# od1.net
KiCad netlist of a schematic drawn in EAGLE
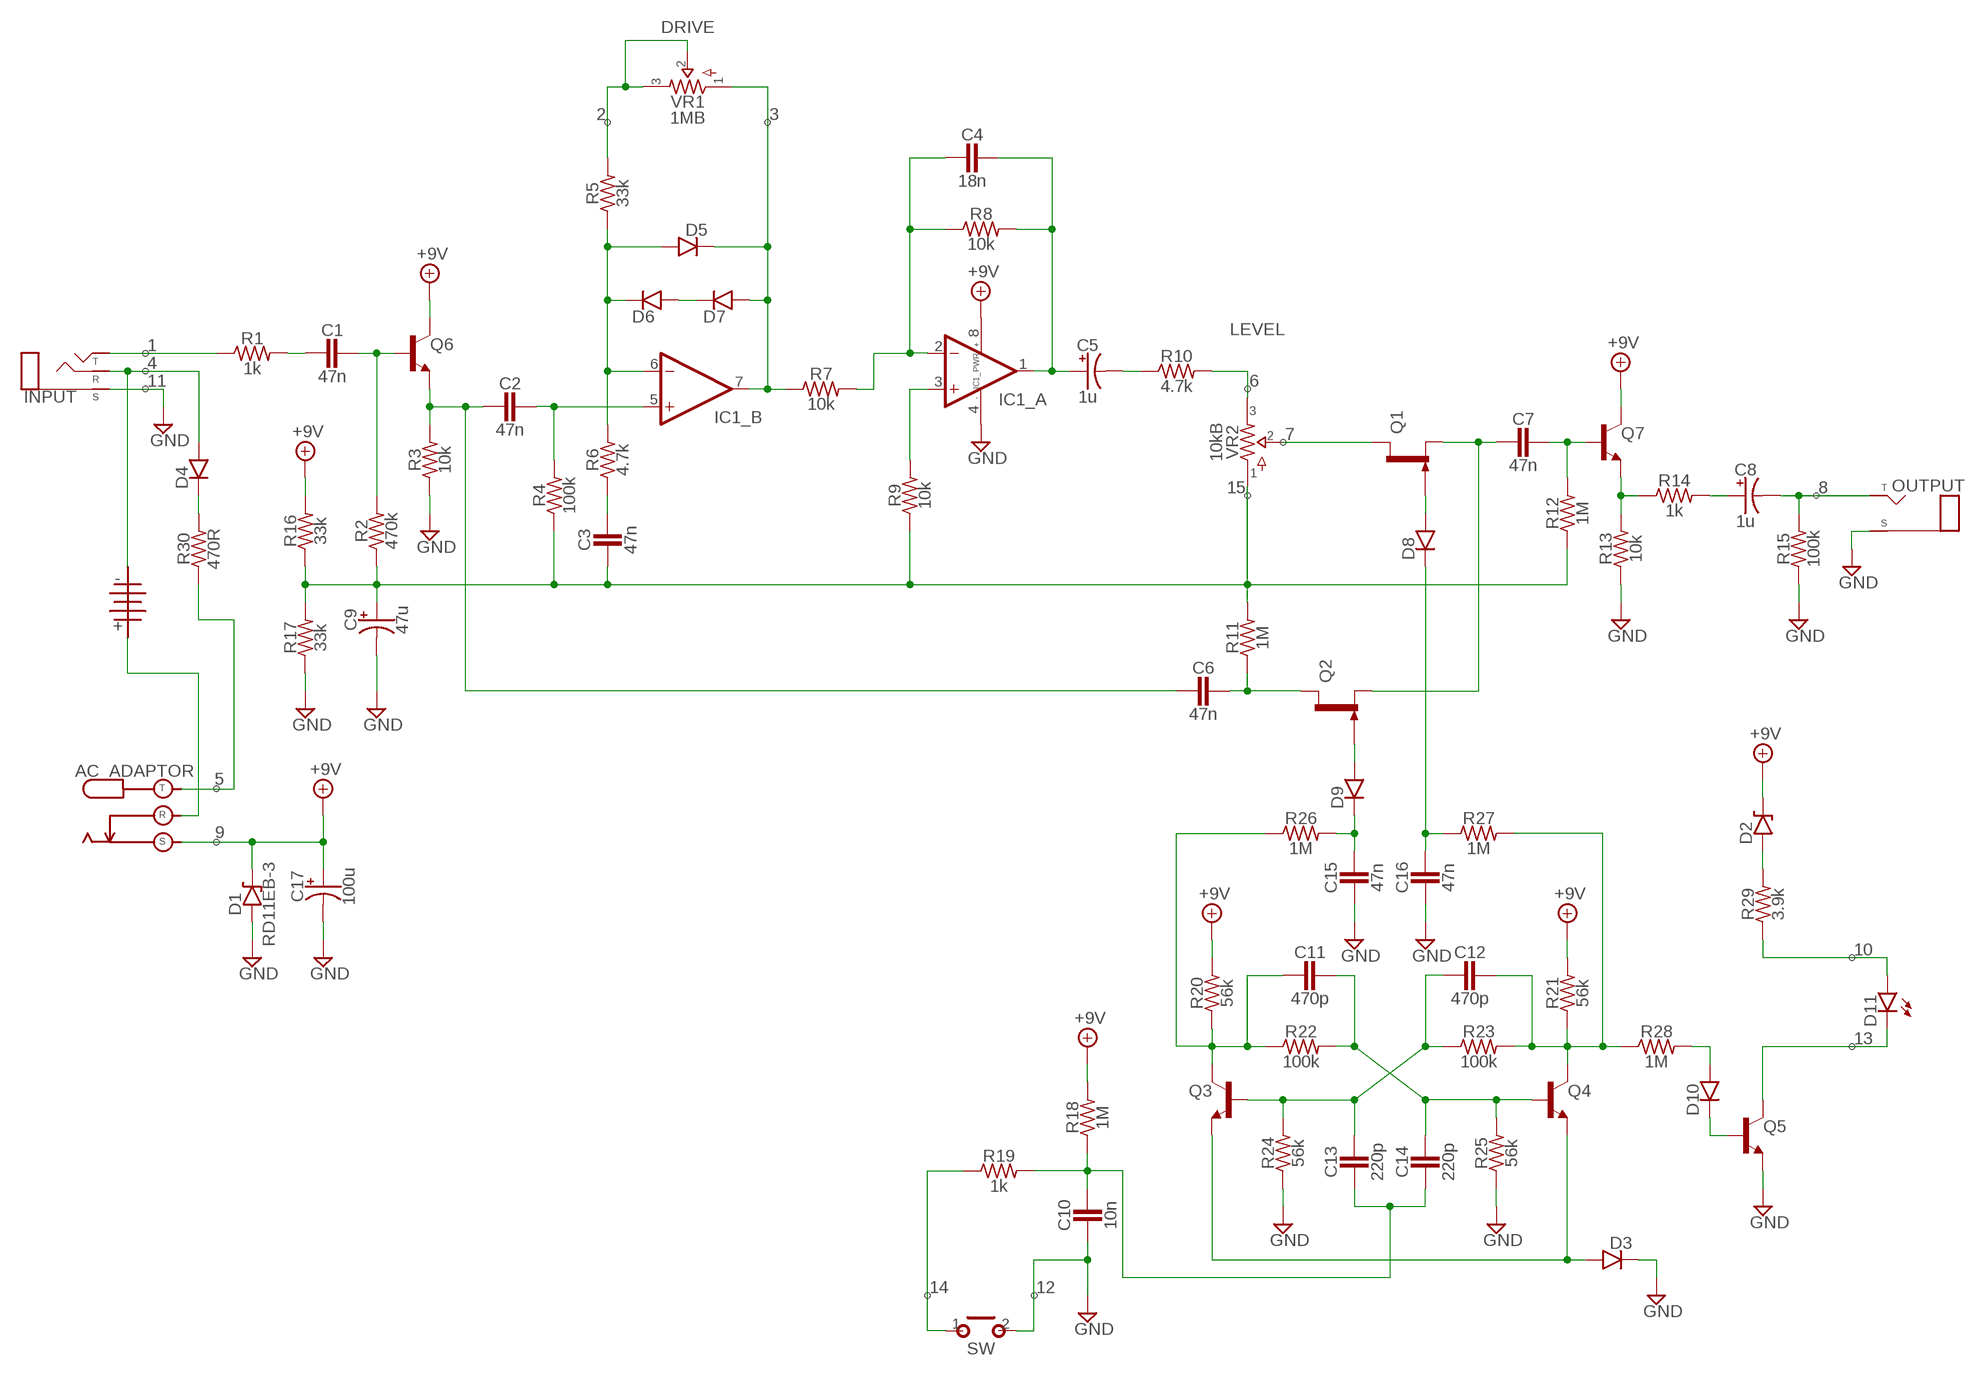
[diagram p0: schematic, sheet 1]

(export (version "E")
  (design (tool "Eeschema 10.0.6"))
  (components
    (comp (ref "1101")
      (value "BATTERY")
      (footprint "eagle-import:TWO_PADS")
      (libsource (lib "eagle-import") (part "BATTERY"))
    )
    (comp (ref "AC_ADAPTOR")
      (value "DC_KOBICONN")
      (footprint "eagle-import:DC_KOBICONN")
      (libsource (lib "eagle-import") (part "DC_KOBICONN"))
    )
    (comp (ref "C1")
      (value "47n")
      (footprint "eagle-import:BOX_SMALL")
      (libsource (lib "eagle-import") (part "CER/FILMBOX.1"))
    )
    (comp (ref "C2")
      (value "47n")
      (footprint "eagle-import:BOX_SMALL")
      (libsource (lib "eagle-import") (part "CER/FILMBOX.1"))
    )
    (comp (ref "C3")
      (value "47n")
      (footprint "eagle-import:BOX_SMALL")
      (libsource (lib "eagle-import") (part "CER/FILMBOX.1"))
    )
    (comp (ref "C4")
      (value "18n")
      (footprint "eagle-import:BOX_SMALL")
      (libsource (lib "eagle-import") (part "CER/FILMBOX.1"))
    )
    (comp (ref "C5")
      (value "1u")
      (footprint "eagle-import:040_020")
      (libsource (lib "eagle-import") (part "0400"))
    )
    (comp (ref "C6")
      (value "47n")
      (footprint "eagle-import:BOX_SMALL")
      (libsource (lib "eagle-import") (part "CER/FILMBOX.1"))
    )
    (comp (ref "C7")
      (value "47n")
      (footprint "eagle-import:BOX_SMALL")
      (libsource (lib "eagle-import") (part "CER/FILMBOX.1"))
    )
    (comp (ref "C8")
      (value "1u")
      (footprint "eagle-import:040_020")
      (libsource (lib "eagle-import") (part "0400"))
    )
    (comp (ref "C9")
      (value "47u")
      (footprint "eagle-import:040_020")
      (libsource (lib "eagle-import") (part "0400"))
    )
    (comp (ref "C10")
      (value "10n")
      (footprint "eagle-import:BOX_SMALL")
      (libsource (lib "eagle-import") (part "CER/FILMBOX.1"))
    )
    (comp (ref "C11")
      (value "470p")
      (footprint "eagle-import:BOX_SMALL")
      (libsource (lib "eagle-import") (part "CER/FILMBOX.1"))
    )
    (comp (ref "C12")
      (value "470p")
      (footprint "eagle-import:BOX_SMALL")
      (libsource (lib "eagle-import") (part "CER/FILMBOX.1"))
    )
    (comp (ref "C13")
      (value "220p")
      (footprint "eagle-import:BOX_SMALL")
      (libsource (lib "eagle-import") (part "CER/FILMBOX.1"))
    )
    (comp (ref "C14")
      (value "220p")
      (footprint "eagle-import:BOX_SMALL")
      (libsource (lib "eagle-import") (part "CER/FILMBOX.1"))
    )
    (comp (ref "C15")
      (value "47n")
      (footprint "eagle-import:BOX_SMALL")
      (libsource (lib "eagle-import") (part "CER/FILMBOX.1"))
    )
    (comp (ref "C16")
      (value "47n")
      (footprint "eagle-import:BOX_SMALL")
      (libsource (lib "eagle-import") (part "CER/FILMBOX.1"))
    )
    (comp (ref "C17")
      (value "100u")
      (footprint "eagle-import:040_020")
      (libsource (lib "eagle-import") (part "0400"))
    )
    (comp (ref "D1")
      (value "RD11EB-3")
      (footprint "eagle-import:DO41-2")
      (libsource (lib "eagle-import") (part "ZENER.2"))
    )
    (comp (ref "D2")
      (value "ZENER.2")
      (footprint "eagle-import:DO41-2")
      (libsource (lib "eagle-import") (part "ZENER.2"))
    )
    (comp (ref "D3")
      (value "DO35.2")
      (footprint "eagle-import:DO35-2")
      (libsource (lib "eagle-import") (part "DO35.2"))
    )
    (comp (ref "D4")
      (value "DO35.2")
      (footprint "eagle-import:DO35-2")
      (libsource (lib "eagle-import") (part "DO35.2"))
    )
    (comp (ref "D5")
      (value "DO35.2")
      (footprint "eagle-import:DO35-2")
      (libsource (lib "eagle-import") (part "DO35.2"))
    )
    (comp (ref "D6")
      (value "DO35.2")
      (footprint "eagle-import:DO35-2")
      (libsource (lib "eagle-import") (part "DO35.2"))
    )
    (comp (ref "D7")
      (value "DO35.2")
      (footprint "eagle-import:DO35-2")
      (libsource (lib "eagle-import") (part "DO35.2"))
    )
    (comp (ref "D8")
      (value "DO35.2")
      (footprint "eagle-import:DO35-2")
      (libsource (lib "eagle-import") (part "DO35.2"))
    )
    (comp (ref "D9")
      (value "DO35.2")
      (footprint "eagle-import:DO35-2")
      (libsource (lib "eagle-import") (part "DO35.2"))
    )
    (comp (ref "D10")
      (value "DO35.2")
      (footprint "eagle-import:DO35-2")
      (libsource (lib "eagle-import") (part "DO35.2"))
    )
    (comp (ref "D11")
      (value "SLP1358")
      (footprint "eagle-import:3MM_D")
      (libsource (lib "eagle-import") (part "LED"))
    )
    (comp (ref "IC1")
      (value "DUALTH")
      (footprint "eagle-import:DIL0")
      (libsource (lib "eagle-import") (part "DUALTH"))
    )
    (comp (ref "INPUT")
      (value "STEREO3PADS")
      (footprint "eagle-import:THREEPADS")
      (libsource (lib "eagle-import") (part "STEREO3PADS"))
    )
    (comp (ref "OUTPUT")
      (value "MONO")
      (footprint "eagle-import:TWO_PADS")
      (libsource (lib "eagle-import") (part "MONO"))
    )
    (comp (ref "Q1")
      (value "2N5457")
      (footprint "eagle-import:TO92-")
      (libsource (lib "eagle-import") (part "2N5457"))
    )
    (comp (ref "Q2")
      (value "2N5457")
      (footprint "eagle-import:TO92-")
      (libsource (lib "eagle-import") (part "2N5457"))
    )
    (comp (ref "Q3")
      (value "2SC828A")
      (footprint "eagle-import:TO92-")
      (libsource (lib "eagle-import") (part "2SC828A"))
    )
    (comp (ref "Q4")
      (value "2SC828A")
      (footprint "eagle-import:TO92-")
      (libsource (lib "eagle-import") (part "2SC828A"))
    )
    (comp (ref "Q5")
      (value "2SC828A")
      (footprint "eagle-import:TO92-")
      (libsource (lib "eagle-import") (part "2SC828A"))
    )
    (comp (ref "Q6")
      (value "2SC828A")
      (footprint "eagle-import:TO92-")
      (libsource (lib "eagle-import") (part "2SC828A"))
    )
    (comp (ref "Q7")
      (value "2SC828A")
      (footprint "eagle-import:TO92-")
      (libsource (lib "eagle-import") (part "2SC828A"))
    )
    (comp (ref "R1")
      (value "1k")
      (footprint "eagle-import:R0207_3")
      (libsource (lib "eagle-import") (part "R_.3B"))
    )
    (comp (ref "R2")
      (value "470k")
      (footprint "eagle-import:R0207_3")
      (libsource (lib "eagle-import") (part "R_.3B"))
    )
    (comp (ref "R3")
      (value "10k")
      (footprint "eagle-import:R0207_3")
      (libsource (lib "eagle-import") (part "R_.3B"))
    )
    (comp (ref "R4")
      (value "100k")
      (footprint "eagle-import:R0207_3")
      (libsource (lib "eagle-import") (part "R_.3B"))
    )
    (comp (ref "R5")
      (value "33k")
      (footprint "eagle-import:R0207_3")
      (libsource (lib "eagle-import") (part "R_.3B"))
    )
    (comp (ref "R6")
      (value "4.7k")
      (footprint "eagle-import:R0207_3")
      (libsource (lib "eagle-import") (part "R_.3B"))
    )
    (comp (ref "R7")
      (value "10k")
      (footprint "eagle-import:R0207_3")
      (libsource (lib "eagle-import") (part "R_.3B"))
    )
    (comp (ref "R8")
      (value "10k")
      (footprint "eagle-import:R0207_3")
      (libsource (lib "eagle-import") (part "R_.3B"))
    )
    (comp (ref "R9")
      (value "10k")
      (footprint "eagle-import:R0207_3")
      (libsource (lib "eagle-import") (part "R_.3B"))
    )
    (comp (ref "R10")
      (value "4.7k")
      (footprint "eagle-import:R0207_3")
      (libsource (lib "eagle-import") (part "R_.3B"))
    )
    (comp (ref "R11")
      (value "1M")
      (footprint "eagle-import:R0207_3")
      (libsource (lib "eagle-import") (part "R_.3B"))
    )
    (comp (ref "R12")
      (value "1M")
      (footprint "eagle-import:R0207_3")
      (libsource (lib "eagle-import") (part "R_.3B"))
    )
    (comp (ref "R13")
      (value "10k")
      (footprint "eagle-import:R0207_3")
      (libsource (lib "eagle-import") (part "R_.3B"))
    )
    (comp (ref "R14")
      (value "1k")
      (footprint "eagle-import:R0207_3")
      (libsource (lib "eagle-import") (part "R_.3B"))
    )
    (comp (ref "R15")
      (value "100k")
      (footprint "eagle-import:R0207_3")
      (libsource (lib "eagle-import") (part "R_.3B"))
    )
    (comp (ref "R16")
      (value "33k")
      (footprint "eagle-import:R0207_3")
      (libsource (lib "eagle-import") (part "R_.3B"))
    )
    (comp (ref "R17")
      (value "33k")
      (footprint "eagle-import:R0207_3")
      (libsource (lib "eagle-import") (part "R_.3B"))
    )
    (comp (ref "R18")
      (value "1M")
      (footprint "eagle-import:R0207_3")
      (libsource (lib "eagle-import") (part "R_.3B"))
    )
    (comp (ref "R19")
      (value "1k")
      (footprint "eagle-import:R0207_3")
      (libsource (lib "eagle-import") (part "R_.3B"))
    )
    (comp (ref "R20")
      (value "56k")
      (footprint "eagle-import:R0207_3")
      (libsource (lib "eagle-import") (part "R_.3B"))
    )
    (comp (ref "R21")
      (value "56k")
      (footprint "eagle-import:R0207_3")
      (libsource (lib "eagle-import") (part "R_.3B"))
    )
    (comp (ref "R22")
      (value "100k")
      (footprint "eagle-import:R0207_3")
      (libsource (lib "eagle-import") (part "R_.3B"))
    )
    (comp (ref "R23")
      (value "100k")
      (footprint "eagle-import:R0207_3")
      (libsource (lib "eagle-import") (part "R_.3B"))
    )
    (comp (ref "R24")
      (value "56k")
      (footprint "eagle-import:R0207_3")
      (libsource (lib "eagle-import") (part "R_.3B"))
    )
    (comp (ref "R25")
      (value "56k")
      (footprint "eagle-import:R0207_3")
      (libsource (lib "eagle-import") (part "R_.3B"))
    )
    (comp (ref "R26")
      (value "1M")
      (footprint "eagle-import:R0207_3")
      (libsource (lib "eagle-import") (part "R_.3B"))
    )
    (comp (ref "R27")
      (value "1M")
      (footprint "eagle-import:R0207_3")
      (libsource (lib "eagle-import") (part "R_.3B"))
    )
    (comp (ref "R28")
      (value "1M")
      (footprint "eagle-import:R0207_3")
      (libsource (lib "eagle-import") (part "R_.3B"))
    )
    (comp (ref "R29")
      (value "3.9k")
      (footprint "eagle-import:R0207_3")
      (libsource (lib "eagle-import") (part "R_.3B"))
    )
    (comp (ref "R30")
      (value "470R")
      (footprint "eagle-import:R0207_3")
      (libsource (lib "eagle-import") (part "R_.3B"))
    )
    (comp (ref "SW")
      (value "MOMENTARY")
      (footprint "eagle-import:SPST")
      (libsource (lib "eagle-import") (part "MOMENTARY"))
    )
    (comp (ref "VR1")
      (value "1MB")
      (footprint "eagle-import:16MM")
      (libsource (lib "eagle-import") (part "POTS16MM"))
    )
    (comp (ref "VR2")
      (value "10kB")
      (footprint "eagle-import:16MM")
      (libsource (lib "eagle-import") (part "POTS16MM"))
    )
  )
  (nets
    (net (code "1") (name "+9V") (class "Default")
      (node (ref "AC_ADAPTOR") (pin "S") (pinfunction "S_S") (pintype "bidirectional"))
      (node (ref "C17") (pin "+") (pinfunction "+_+") (pintype "passive"))
      (node (ref "D1") (pin "C") (pinfunction "C_C") (pintype "passive"))
      (node (ref "D2") (pin "C") (pinfunction "C_C") (pintype "passive"))
      (node (ref "IC1") (pin "8") (pinfunction "V+_8") (pintype "power_in"))
      (node (ref "Q6") (pin "2") (pinfunction "C_2") (pintype "passive"))
      (node (ref "Q7") (pin "2") (pinfunction "C_2") (pintype "passive"))
      (node (ref "R16") (pin "2") (pinfunction "2_2") (pintype "passive"))
      (node (ref "R18") (pin "2") (pinfunction "2_2") (pintype "passive"))
      (node (ref "R20") (pin "2") (pinfunction "2_2") (pintype "passive"))
      (node (ref "R21") (pin "2") (pinfunction "2_2") (pintype "passive"))
    )
    (net (code "2") (name "GND") (class "Default")
      (node (ref "C10") (pin "2") (pinfunction "2_2") (pintype "passive"))
      (node (ref "C15") (pin "2") (pinfunction "2_2") (pintype "passive"))
      (node (ref "C16") (pin "2") (pinfunction "2_2") (pintype "passive"))
      (node (ref "C17") (pin "-") (pinfunction "-_-") (pintype "passive"))
      (node (ref "C9") (pin "-") (pinfunction "-_-") (pintype "passive"))
      (node (ref "D1") (pin "A") (pinfunction "A_A") (pintype "passive"))
      (node (ref "D3") (pin "C") (pinfunction "C_C") (pintype "passive"))
      (node (ref "IC1") (pin "4") (pinfunction "V-_4") (pintype "power_in"))
      (node (ref "INPUT") (pin "SLEEVE") (pinfunction "S_SLEEVE") (pintype "passive"))
      (node (ref "OUTPUT") (pin "S") (pinfunction "SLEEVE_S") (pintype "passive"))
      (node (ref "Q5") (pin "3") (pinfunction "E_3") (pintype "passive"))
      (node (ref "R13") (pin "1") (pinfunction "1_1") (pintype "passive"))
      (node (ref "R15") (pin "1") (pinfunction "1_1") (pintype "passive"))
      (node (ref "R17") (pin "1") (pinfunction "1_1") (pintype "passive"))
      (node (ref "R24") (pin "1") (pinfunction "1_1") (pintype "passive"))
      (node (ref "R25") (pin "1") (pinfunction "1_1") (pintype "passive"))
      (node (ref "R3") (pin "1") (pinfunction "1_1") (pintype "passive"))
      (node (ref "SW") (pin "2") (pinfunction "S_2") (pintype "passive"))
    )
    (net (code "3") (name "Net-(1101-P$1)") (class "Default")
      (node (ref "1101") (pin "T") (pinfunction "P$1_T") (pintype "bidirectional"))
      (node (ref "AC_ADAPTOR") (pin "R") (pinfunction "R_R") (pintype "bidirectional"))
    )
    (net (code "4") (name "Net-(1101-P$2)") (class "Default")
      (node (ref "1101") (pin "S") (pinfunction "P$2_S") (pintype "bidirectional"))
      (node (ref "D4") (pin "A") (pinfunction "A_A") (pintype "passive"))
      (node (ref "INPUT") (pin "RING") (pinfunction "R_RING") (pintype "passive"))
    )
    (net (code "5") (name "Net-(AC_ADAPTOR-PadT)") (class "Default")
      (node (ref "AC_ADAPTOR") (pin "T") (pinfunction "T_T") (pintype "bidirectional"))
      (node (ref "R30") (pin "1") (pinfunction "1_1") (pintype "passive"))
    )
    (net (code "6") (name "Net-(C1-Pad2)") (class "Default")
      (node (ref "C1") (pin "2") (pinfunction "2_2") (pintype "passive"))
      (node (ref "R1") (pin "2") (pinfunction "2_2") (pintype "passive"))
    )
    (net (code "7") (name "Net-(C3-Pad1)") (class "Default")
      (node (ref "C3") (pin "1") (pinfunction "1_1") (pintype "passive"))
      (node (ref "R6") (pin "1") (pinfunction "1_1") (pintype "passive"))
    )
    (net (code "8") (name "Net-(C3-Pad2)") (class "Default")
      (node (ref "C3") (pin "2") (pinfunction "2_2") (pintype "passive"))
      (node (ref "C9") (pin "+") (pinfunction "+_+") (pintype "passive"))
      (node (ref "R11") (pin "2") (pinfunction "2_2") (pintype "passive"))
      (node (ref "R12") (pin "1") (pinfunction "1_1") (pintype "passive"))
      (node (ref "R16") (pin "1") (pinfunction "1_1") (pintype "passive"))
      (node (ref "R17") (pin "2") (pinfunction "2_2") (pintype "passive"))
      (node (ref "R2") (pin "1") (pinfunction "1_1") (pintype "passive"))
      (node (ref "R4") (pin "1") (pinfunction "1_1") (pintype "passive"))
      (node (ref "R9") (pin "1") (pinfunction "1_1") (pintype "passive"))
      (node (ref "VR2") (pin "1") (pinfunction "1_1") (pintype "passive"))
    )
    (net (code "9") (name "Net-(C5-Pad-)") (class "Default")
      (node (ref "C5") (pin "-") (pinfunction "-_-") (pintype "passive"))
      (node (ref "R10") (pin "1") (pinfunction "1_1") (pintype "passive"))
    )
    (net (code "10") (name "Net-(C8-Pad+)") (class "Default")
      (node (ref "C8") (pin "+") (pinfunction "+_+") (pintype "passive"))
      (node (ref "R14") (pin "2") (pinfunction "2_2") (pintype "passive"))
    )
    (net (code "11") (name "Net-(C10-Pad1)") (class "Default")
      (node (ref "C10") (pin "1") (pinfunction "1_1") (pintype "passive"))
      (node (ref "C13") (pin "2") (pinfunction "2_2") (pintype "passive"))
      (node (ref "C14") (pin "2") (pinfunction "2_2") (pintype "passive"))
      (node (ref "R18") (pin "1") (pinfunction "1_1") (pintype "passive"))
      (node (ref "R19") (pin "2") (pinfunction "2_2") (pintype "passive"))
    )
    (net (code "12") (name "Net-(C15-Pad1)") (class "Default")
      (node (ref "C15") (pin "1") (pinfunction "1_1") (pintype "passive"))
      (node (ref "D9") (pin "C") (pinfunction "C_C") (pintype "passive"))
      (node (ref "R26") (pin "2") (pinfunction "2_2") (pintype "passive"))
    )
    (net (code "13") (name "Net-(C16-Pad1)") (class "Default")
      (node (ref "C16") (pin "1") (pinfunction "1_1") (pintype "passive"))
      (node (ref "D8") (pin "C") (pinfunction "C_C") (pintype "passive"))
      (node (ref "R27") (pin "1") (pinfunction "1_1") (pintype "passive"))
    )
    (net (code "14") (name "Net-(D2-PadA)") (class "Default")
      (node (ref "D2") (pin "A") (pinfunction "A_A") (pintype "passive"))
      (node (ref "R29") (pin "2") (pinfunction "2_2") (pintype "passive"))
    )
    (net (code "15") (name "Net-(D4-PadC)") (class "Default")
      (node (ref "D4") (pin "C") (pinfunction "C_C") (pintype "passive"))
      (node (ref "R30") (pin "2") (pinfunction "2_2") (pintype "passive"))
    )
    (net (code "16") (name "Net-(D6-PadA)") (class "Default")
      (node (ref "D6") (pin "A") (pinfunction "A_A") (pintype "passive"))
      (node (ref "D7") (pin "C") (pinfunction "C_C") (pintype "passive"))
    )
    (net (code "17") (name "Net-(D10-PadA)") (class "Default")
      (node (ref "D10") (pin "A") (pinfunction "A_A") (pintype "passive"))
      (node (ref "R28") (pin "2") (pinfunction "2_2") (pintype "passive"))
    )
    (net (code "18") (name "Net-(D11-A)") (class "Default")
      (node (ref "D11") (pin "ANODE") (pinfunction "A_ANODE") (pintype "passive"))
      (node (ref "R29") (pin "1") (pinfunction "1_1") (pintype "passive"))
    )
    (net (code "19") (name "Net-(D11-C)") (class "Default")
      (node (ref "D11") (pin "P$1") (pinfunction "C_P$1") (pintype "passive"))
      (node (ref "Q5") (pin "2") (pinfunction "C_2") (pintype "passive"))
    )
    (net (code "20") (name "Net-(IC1A-+IN)") (class "Default")
      (node (ref "IC1") (pin "3") (pinfunction "+IN_3") (pintype "input"))
      (node (ref "R9") (pin "2") (pinfunction "2_2") (pintype "passive"))
    )
    (net (code "21") (name "Net-(IC1A--IN)") (class "Default")
      (node (ref "C4") (pin "2") (pinfunction "2_2") (pintype "passive"))
      (node (ref "IC1") (pin "2") (pinfunction "-IN_2") (pintype "input"))
      (node (ref "R7") (pin "2") (pinfunction "2_2") (pintype "passive"))
      (node (ref "R8") (pin "1") (pinfunction "1_1") (pintype "passive"))
    )
    (net (code "22") (name "Net-(IC1A-OUT)") (class "Default")
      (node (ref "C4") (pin "1") (pinfunction "1_1") (pintype "passive"))
      (node (ref "C5") (pin "+") (pinfunction "+_+") (pintype "passive"))
      (node (ref "IC1") (pin "1") (pinfunction "OUT_1") (pintype "output"))
      (node (ref "R8") (pin "2") (pinfunction "2_2") (pintype "passive"))
    )
    (net (code "23") (name "Net-(IC1B-+IN)") (class "Default")
      (node (ref "C2") (pin "1") (pinfunction "1_1") (pintype "passive"))
      (node (ref "IC1") (pin "5") (pinfunction "+IN_5") (pintype "input"))
      (node (ref "R4") (pin "2") (pinfunction "2_2") (pintype "passive"))
    )
    (net (code "24") (name "Net-(IC1B--IN)") (class "Default")
      (node (ref "D5") (pin "A") (pinfunction "A_A") (pintype "passive"))
      (node (ref "D6") (pin "C") (pinfunction "C_C") (pintype "passive"))
      (node (ref "IC1") (pin "6") (pinfunction "-IN_6") (pintype "input"))
      (node (ref "R5") (pin "1") (pinfunction "1_1") (pintype "passive"))
      (node (ref "R6") (pin "2") (pinfunction "2_2") (pintype "passive"))
    )
    (net (code "25") (name "Net-(IC1B-OUT)") (class "Default")
      (node (ref "D5") (pin "C") (pinfunction "C_C") (pintype "passive"))
      (node (ref "D7") (pin "A") (pinfunction "A_A") (pintype "passive"))
      (node (ref "IC1") (pin "7") (pinfunction "OUT_7") (pintype "output"))
      (node (ref "R7") (pin "1") (pinfunction "1_1") (pintype "passive"))
      (node (ref "VR1") (pin "1") (pinfunction "1_1") (pintype "passive"))
    )
    (net (code "26") (name "Net-(INPUT-T)") (class "Default")
      (node (ref "INPUT") (pin "TIP") (pinfunction "T_TIP") (pintype "passive"))
      (node (ref "R1") (pin "1") (pinfunction "1_1") (pintype "passive"))
    )
    (net (code "27") (name "Net-(OUTPUT-TIP)") (class "Default")
      (node (ref "C8") (pin "-") (pinfunction "-_-") (pintype "passive"))
      (node (ref "OUTPUT") (pin "T") (pinfunction "TIP_T") (pintype "passive"))
      (node (ref "R15") (pin "2") (pinfunction "2_2") (pintype "passive"))
    )
    (net (code "28") (name "Net-(Q1-D)") (class "Default")
      (node (ref "Q1") (pin "3") (pinfunction "D_3") (pintype "passive"))
      (node (ref "VR2") (pin "2") (pinfunction "2_2") (pintype "passive"))
    )
    (net (code "29") (name "Net-(Q1-G)") (class "Default")
      (node (ref "D8") (pin "A") (pinfunction "A_A") (pintype "passive"))
      (node (ref "Q1") (pin "1") (pinfunction "G_1") (pintype "passive"))
    )
    (net (code "30") (name "Net-(Q1-S)") (class "Default")
      (node (ref "C7") (pin "2") (pinfunction "2_2") (pintype "passive"))
      (node (ref "Q1") (pin "2") (pinfunction "S_2") (pintype "passive"))
      (node (ref "Q2") (pin "2") (pinfunction "S_2") (pintype "passive"))
    )
    (net (code "31") (name "Net-(Q2-D)") (class "Default")
      (node (ref "C6") (pin "1") (pinfunction "1_1") (pintype "passive"))
      (node (ref "Q2") (pin "3") (pinfunction "D_3") (pintype "passive"))
      (node (ref "R11") (pin "1") (pinfunction "1_1") (pintype "passive"))
    )
    (net (code "32") (name "Net-(Q2-G)") (class "Default")
      (node (ref "D9") (pin "A") (pinfunction "A_A") (pintype "passive"))
      (node (ref "Q2") (pin "1") (pinfunction "G_1") (pintype "passive"))
    )
    (net (code "33") (name "Net-(Q3-B)") (class "Default")
      (node (ref "C12") (pin "2") (pinfunction "2_2") (pintype "passive"))
      (node (ref "C13") (pin "1") (pinfunction "1_1") (pintype "passive"))
      (node (ref "Q3") (pin "1") (pinfunction "B_1") (pintype "passive"))
      (node (ref "R23") (pin "1") (pinfunction "1_1") (pintype "passive"))
      (node (ref "R24") (pin "2") (pinfunction "2_2") (pintype "passive"))
    )
    (net (code "34") (name "Net-(Q3-C)") (class "Default")
      (node (ref "C11") (pin "2") (pinfunction "2_2") (pintype "passive"))
      (node (ref "Q3") (pin "2") (pinfunction "C_2") (pintype "passive"))
      (node (ref "R20") (pin "1") (pinfunction "1_1") (pintype "passive"))
      (node (ref "R22") (pin "1") (pinfunction "1_1") (pintype "passive"))
      (node (ref "R26") (pin "1") (pinfunction "1_1") (pintype "passive"))
    )
    (net (code "35") (name "Net-(Q3-E)") (class "Default")
      (node (ref "D3") (pin "A") (pinfunction "A_A") (pintype "passive"))
      (node (ref "Q3") (pin "3") (pinfunction "E_3") (pintype "passive"))
      (node (ref "Q4") (pin "3") (pinfunction "E_3") (pintype "passive"))
    )
    (net (code "36") (name "Net-(Q4-B)") (class "Default")
      (node (ref "C11") (pin "1") (pinfunction "1_1") (pintype "passive"))
      (node (ref "C14") (pin "1") (pinfunction "1_1") (pintype "passive"))
      (node (ref "Q4") (pin "1") (pinfunction "B_1") (pintype "passive"))
      (node (ref "R22") (pin "2") (pinfunction "2_2") (pintype "passive"))
      (node (ref "R25") (pin "2") (pinfunction "2_2") (pintype "passive"))
    )
    (net (code "37") (name "Net-(Q4-C)") (class "Default")
      (node (ref "C12") (pin "1") (pinfunction "1_1") (pintype "passive"))
      (node (ref "Q4") (pin "2") (pinfunction "C_2") (pintype "passive"))
      (node (ref "R21") (pin "1") (pinfunction "1_1") (pintype "passive"))
      (node (ref "R23") (pin "2") (pinfunction "2_2") (pintype "passive"))
      (node (ref "R27") (pin "2") (pinfunction "2_2") (pintype "passive"))
      (node (ref "R28") (pin "1") (pinfunction "1_1") (pintype "passive"))
    )
    (net (code "38") (name "Net-(Q5-B)") (class "Default")
      (node (ref "D10") (pin "C") (pinfunction "C_C") (pintype "passive"))
      (node (ref "Q5") (pin "1") (pinfunction "B_1") (pintype "passive"))
    )
    (net (code "39") (name "Net-(Q6-B)") (class "Default")
      (node (ref "C1") (pin "1") (pinfunction "1_1") (pintype "passive"))
      (node (ref "Q6") (pin "1") (pinfunction "B_1") (pintype "passive"))
      (node (ref "R2") (pin "2") (pinfunction "2_2") (pintype "passive"))
    )
    (net (code "40") (name "Net-(Q6-E)") (class "Default")
      (node (ref "C2") (pin "2") (pinfunction "2_2") (pintype "passive"))
      (node (ref "C6") (pin "2") (pinfunction "2_2") (pintype "passive"))
      (node (ref "Q6") (pin "3") (pinfunction "E_3") (pintype "passive"))
      (node (ref "R3") (pin "2") (pinfunction "2_2") (pintype "passive"))
    )
    (net (code "41") (name "Net-(Q7-B)") (class "Default")
      (node (ref "C7") (pin "1") (pinfunction "1_1") (pintype "passive"))
      (node (ref "Q7") (pin "1") (pinfunction "B_1") (pintype "passive"))
      (node (ref "R12") (pin "2") (pinfunction "2_2") (pintype "passive"))
    )
    (net (code "42") (name "Net-(Q7-E)") (class "Default")
      (node (ref "Q7") (pin "3") (pinfunction "E_3") (pintype "passive"))
      (node (ref "R13") (pin "2") (pinfunction "2_2") (pintype "passive"))
      (node (ref "R14") (pin "1") (pinfunction "1_1") (pintype "passive"))
    )
    (net (code "43") (name "Net-(R5-Pad2)") (class "Default")
      (node (ref "R5") (pin "2") (pinfunction "2_2") (pintype "passive"))
      (node (ref "VR1") (pin "2") (pinfunction "2_2") (pintype "passive"))
      (node (ref "VR1") (pin "3") (pinfunction "3_3") (pintype "passive"))
    )
    (net (code "44") (name "Net-(R10-Pad2)") (class "Default")
      (node (ref "R10") (pin "2") (pinfunction "2_2") (pintype "passive"))
      (node (ref "VR2") (pin "3") (pinfunction "3_3") (pintype "passive"))
    )
    (net (code "45") (name "Net-(SW-P)") (class "Default")
      (node (ref "R19") (pin "1") (pinfunction "1_1") (pintype "passive"))
      (node (ref "SW") (pin "1") (pinfunction "P_1") (pintype "passive"))
    )
  )
)
